# scheme.net
KiCad netlist of a schematic drawn in EAGLE
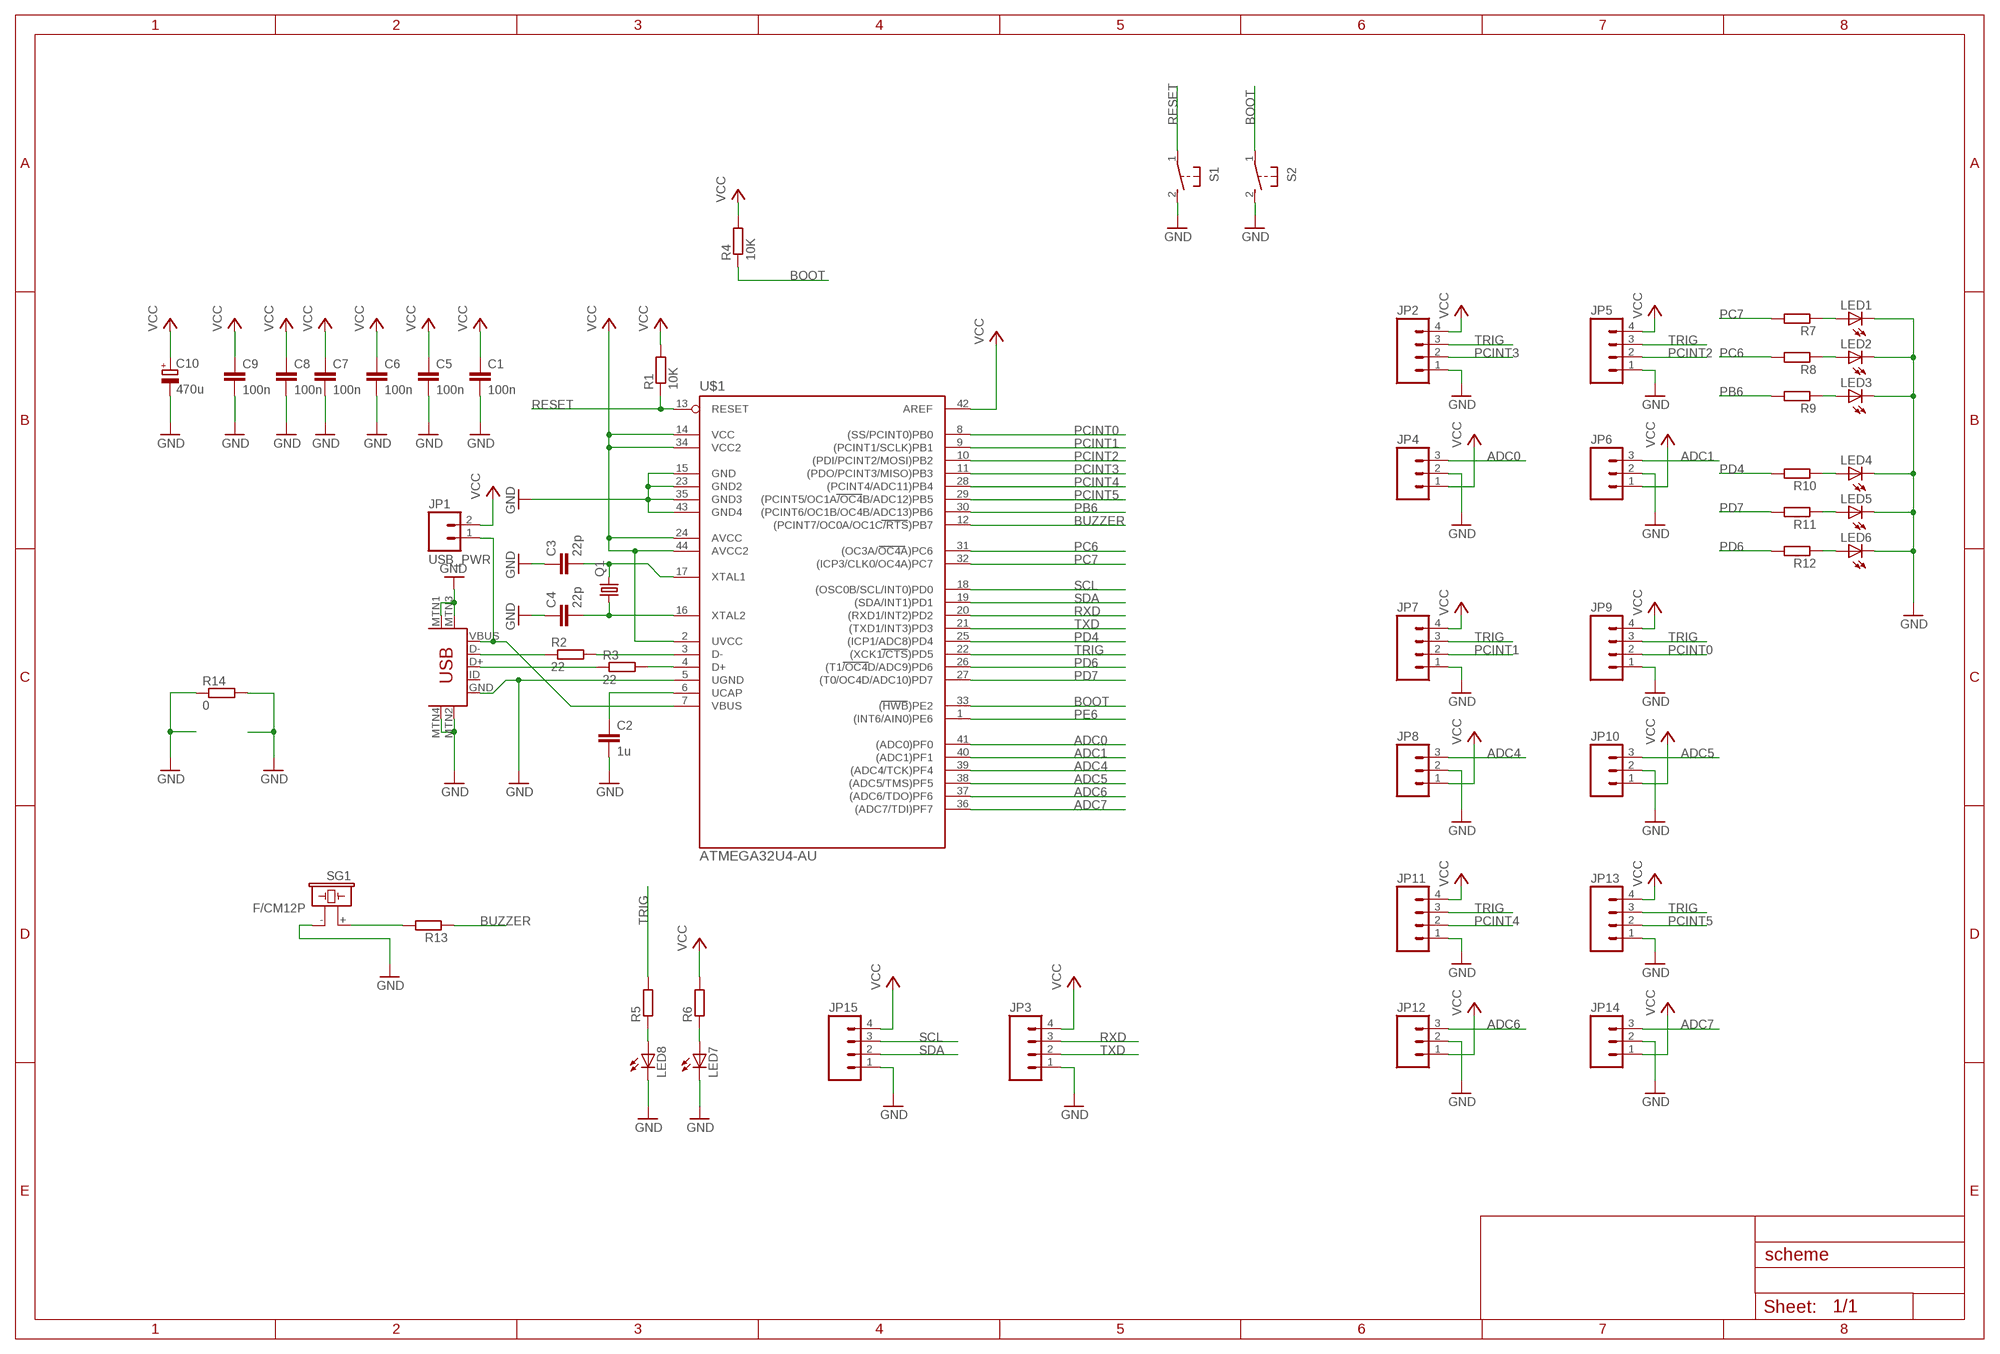
[diagram p0: schematic, sheet 1]

(export (version "E")
  (design (tool "Eeschema 10.0.6"))
  (components
    (comp (ref "C1")
      (value "100n")
      (footprint "eagle-import:C0805")
      (libsource (lib "eagle-import") (part "C-EUC0805"))
    )
    (comp (ref "C2")
      (value "1u")
      (footprint "eagle-import:C0805")
      (libsource (lib "eagle-import") (part "C-EUC0805"))
    )
    (comp (ref "C3")
      (value "22p")
      (footprint "eagle-import:C0805")
      (libsource (lib "eagle-import") (part "C-EUC0805"))
    )
    (comp (ref "C4")
      (value "22p")
      (footprint "eagle-import:C0805")
      (libsource (lib "eagle-import") (part "C-EUC0805"))
    )
    (comp (ref "C5")
      (value "100n")
      (footprint "eagle-import:C0805")
      (libsource (lib "eagle-import") (part "C-EUC0805"))
    )
    (comp (ref "C6")
      (value "100n")
      (footprint "eagle-import:C0805")
      (libsource (lib "eagle-import") (part "C-EUC0805"))
    )
    (comp (ref "C7")
      (value "100n")
      (footprint "eagle-import:C0805")
      (libsource (lib "eagle-import") (part "C-EUC0805"))
    )
    (comp (ref "C8")
      (value "100n")
      (footprint "eagle-import:C0805")
      (libsource (lib "eagle-import") (part "C-EUC0805"))
    )
    (comp (ref "C9")
      (value "100n")
      (footprint "eagle-import:C0805")
      (libsource (lib "eagle-import") (part "C-EUC0805"))
    )
    (comp (ref "C10")
      (value "470u")
      (footprint "eagle-import:E3,5-8")
      (libsource (lib "eagle-import") (part "CPOL-EUE3.5-8"))
    )
    (comp (ref "JP1")
      (value "USB_PWR")
      (footprint "eagle-import:1X02")
      (libsource (lib "eagle-import") (part "M02PTH"))
    )
    (comp (ref "JP2")
      (value "M04PTH")
      (footprint "eagle-import:1X04")
      (libsource (lib "eagle-import") (part "M04PTH"))
    )
    (comp (ref "JP3")
      (value "M04PTH")
      (footprint "eagle-import:1X04")
      (libsource (lib "eagle-import") (part "M04PTH"))
    )
    (comp (ref "JP4")
      (value "M03PTH")
      (footprint "eagle-import:1X03")
      (libsource (lib "eagle-import") (part "M03PTH"))
    )
    (comp (ref "JP5")
      (value "M04PTH")
      (footprint "eagle-import:1X04")
      (libsource (lib "eagle-import") (part "M04PTH"))
    )
    (comp (ref "JP6")
      (value "M03PTH")
      (footprint "eagle-import:1X03")
      (libsource (lib "eagle-import") (part "M03PTH"))
    )
    (comp (ref "JP7")
      (value "M04PTH")
      (footprint "eagle-import:1X04")
      (libsource (lib "eagle-import") (part "M04PTH"))
    )
    (comp (ref "JP8")
      (value "M03PTH")
      (footprint "eagle-import:1X03")
      (libsource (lib "eagle-import") (part "M03PTH"))
    )
    (comp (ref "JP9")
      (value "M04PTH")
      (footprint "eagle-import:1X04")
      (libsource (lib "eagle-import") (part "M04PTH"))
    )
    (comp (ref "JP10")
      (value "M03PTH")
      (footprint "eagle-import:1X03")
      (libsource (lib "eagle-import") (part "M03PTH"))
    )
    (comp (ref "JP11")
      (value "M04PTH")
      (footprint "eagle-import:1X04")
      (libsource (lib "eagle-import") (part "M04PTH"))
    )
    (comp (ref "JP12")
      (value "M03PTH")
      (footprint "eagle-import:1X03")
      (libsource (lib "eagle-import") (part "M03PTH"))
    )
    (comp (ref "JP13")
      (value "M04PTH")
      (footprint "eagle-import:1X04")
      (libsource (lib "eagle-import") (part "M04PTH"))
    )
    (comp (ref "JP14")
      (value "M03PTH")
      (footprint "eagle-import:1X03")
      (libsource (lib "eagle-import") (part "M03PTH"))
    )
    (comp (ref "JP15")
      (value "M04PTH")
      (footprint "eagle-import:1X04")
      (libsource (lib "eagle-import") (part "M04PTH"))
    )
    (comp (ref "LED1")
      (value "LEDSMT1206")
      (footprint "eagle-import:1206")
      (libsource (lib "eagle-import") (part "LEDSMT1206"))
    )
    (comp (ref "LED2")
      (value "LEDSMT1206")
      (footprint "eagle-import:1206")
      (libsource (lib "eagle-import") (part "LEDSMT1206"))
    )
    (comp (ref "LED3")
      (value "LEDSMT1206")
      (footprint "eagle-import:1206")
      (libsource (lib "eagle-import") (part "LEDSMT1206"))
    )
    (comp (ref "LED4")
      (value "LEDSMT1206")
      (footprint "eagle-import:1206")
      (libsource (lib "eagle-import") (part "LEDSMT1206"))
    )
    (comp (ref "LED5")
      (value "LEDSMT1206")
      (footprint "eagle-import:1206")
      (libsource (lib "eagle-import") (part "LEDSMT1206"))
    )
    (comp (ref "LED6")
      (value "LEDSMT1206")
      (footprint "eagle-import:1206")
      (libsource (lib "eagle-import") (part "LEDSMT1206"))
    )
    (comp (ref "LED7")
      (value "LEDSMT1206")
      (footprint "eagle-import:1206")
      (libsource (lib "eagle-import") (part "LEDSMT1206"))
    )
    (comp (ref "LED8")
      (value "LEDSMT1206")
      (footprint "eagle-import:1206")
      (libsource (lib "eagle-import") (part "LEDSMT1206"))
    )
    (comp (ref "Q1")
      (value "CRYSTALHC49S")
      (footprint "eagle-import:HC49_S")
      (libsource (lib "eagle-import") (part "CRYSTALHC49S"))
    )
    (comp (ref "R1")
      (value "10K")
      (footprint "eagle-import:R0805")
      (libsource (lib "eagle-import") (part "R-EU_R0805"))
    )
    (comp (ref "R2")
      (value "22")
      (footprint "eagle-import:R0805")
      (libsource (lib "eagle-import") (part "R-EU_R0805"))
    )
    (comp (ref "R3")
      (value "22")
      (footprint "eagle-import:R0805")
      (libsource (lib "eagle-import") (part "R-EU_R0805"))
    )
    (comp (ref "R4")
      (value "10K")
      (footprint "eagle-import:R0805")
      (libsource (lib "eagle-import") (part "R-EU_R0805"))
    )
    (comp (ref "R5")
      (value "R-EU_M0805")
      (footprint "eagle-import:M0805")
      (libsource (lib "eagle-import") (part "R-EU_M0805"))
    )
    (comp (ref "R6")
      (value "R-EU_M0805")
      (footprint "eagle-import:M0805")
      (libsource (lib "eagle-import") (part "R-EU_M0805"))
    )
    (comp (ref "R7")
      (value "R-EU_M0805")
      (footprint "eagle-import:M0805")
      (libsource (lib "eagle-import") (part "R-EU_M0805"))
    )
    (comp (ref "R8")
      (value "R-EU_M0805")
      (footprint "eagle-import:M0805")
      (libsource (lib "eagle-import") (part "R-EU_M0805"))
    )
    (comp (ref "R9")
      (value "R-EU_M0805")
      (footprint "eagle-import:M0805")
      (libsource (lib "eagle-import") (part "R-EU_M0805"))
    )
    (comp (ref "R10")
      (value "R-EU_M0805")
      (footprint "eagle-import:M0805")
      (libsource (lib "eagle-import") (part "R-EU_M0805"))
    )
    (comp (ref "R11")
      (value "R-EU_M0805")
      (footprint "eagle-import:M0805")
      (libsource (lib "eagle-import") (part "R-EU_M0805"))
    )
    (comp (ref "R12")
      (value "R-EU_M0805")
      (footprint "eagle-import:M0805")
      (libsource (lib "eagle-import") (part "R-EU_M0805"))
    )
    (comp (ref "R13")
      (value "R-EU_M0805")
      (footprint "eagle-import:M0805")
      (libsource (lib "eagle-import") (part "R-EU_M0805"))
    )
    (comp (ref "R14")
      (value "0")
      (footprint "eagle-import:M1206")
      (libsource (lib "eagle-import") (part "R-EU_M1206"))
    )
    (comp (ref "S1")
      (value "31-XX")
      (footprint "eagle-import:B3F-31XX")
      (fields (field (name "MPN") "B3F-3100"))
      (libsource (lib "eagle-import") (part "31-XX"))
    )
    (comp (ref "S2")
      (value "31-XX")
      (footprint "eagle-import:B3F-31XX")
      (fields (field (name "MPN") "B3F-3100"))
      (libsource (lib "eagle-import") (part "31-XX"))
    )
    (comp (ref "SG1")
      (value "F/CM12P")
      (footprint "eagle-import:F_CM12P")
      (libsource (lib "eagle-import") (part "F/CM12P"))
    )
    (comp (ref "U$1")
      (value "ATMEGA32U4-AU")
      (footprint "eagle-import:TQFP44")
      (libsource (lib "eagle-import") (part "ATMEGA32U4-AU"))
    )
    (comp (ref "U$2")
      (value "USB-MINIB-5PIN")
      (footprint "eagle-import:USB-MINIB")
      (libsource (lib "eagle-import") (part "USB-MINIB-5PIN"))
    )
  )
  (nets
    (net (code "1") (name "/ADC0") (class "Default")
      (node (ref "JP4") (pin "3") (pinfunction "3_3") (pintype "passive"))
      (node (ref "U$1") (pin "41") (pinfunction "(ADC0)PF0_41") (pintype "bidirectional"))
    )
    (net (code "2") (name "/ADC1") (class "Default")
      (node (ref "JP6") (pin "3") (pinfunction "3_3") (pintype "passive"))
      (node (ref "U$1") (pin "40") (pinfunction "(ADC1)PF1_40") (pintype "bidirectional"))
    )
    (net (code "3") (name "/ADC4") (class "Default")
      (node (ref "JP8") (pin "3") (pinfunction "3_3") (pintype "passive"))
      (node (ref "U$1") (pin "39") (pinfunction "(ADC4/TCK)PF4_39") (pintype "bidirectional"))
    )
    (net (code "4") (name "/ADC5") (class "Default")
      (node (ref "JP10") (pin "3") (pinfunction "3_3") (pintype "passive"))
      (node (ref "U$1") (pin "38") (pinfunction "(ADC5/TMS)PF5_38") (pintype "bidirectional"))
    )
    (net (code "5") (name "/ADC6") (class "Default")
      (node (ref "JP12") (pin "3") (pinfunction "3_3") (pintype "passive"))
      (node (ref "U$1") (pin "37") (pinfunction "(ADC6/TDO)PF6_37") (pintype "bidirectional"))
    )
    (net (code "6") (name "/ADC7") (class "Default")
      (node (ref "JP14") (pin "3") (pinfunction "3_3") (pintype "passive"))
      (node (ref "U$1") (pin "36") (pinfunction "(ADC7/TDI)PF7_36") (pintype "bidirectional"))
    )
    (net (code "7") (name "/BOOT") (class "Default")
      (node (ref "R4") (pin "1") (pinfunction "1_1") (pintype "passive"))
      (node (ref "S2") (pin "1") (pinfunction "P_1") (pintype "passive"))
      (node (ref "U$1") (pin "33") (pinfunction "(HWB)PE2_33") (pintype "bidirectional"))
    )
    (net (code "8") (name "/BUZZER") (class "Default")
      (node (ref "R13") (pin "1") (pinfunction "1_1") (pintype "passive"))
      (node (ref "U$1") (pin "12") (pinfunction "(PCINT7/OC0A/OC1C/RTS)PB7_12") (pintype "bidirectional"))
    )
    (net (code "9") (name "/PB6") (class "Default")
      (node (ref "R9") (pin "2") (pinfunction "2_2") (pintype "passive"))
      (node (ref "U$1") (pin "30") (pinfunction "(PCINT6/OC1B/OC4B/ADC13)PB6_30") (pintype "bidirectional"))
    )
    (net (code "10") (name "/PC6") (class "Default")
      (node (ref "R8") (pin "2") (pinfunction "2_2") (pintype "passive"))
      (node (ref "U$1") (pin "31") (pinfunction "(OC3A/OC4A)PC6_31") (pintype "bidirectional"))
    )
    (net (code "11") (name "/PC7") (class "Default")
      (node (ref "R7") (pin "2") (pinfunction "2_2") (pintype "passive"))
      (node (ref "U$1") (pin "32") (pinfunction "(ICP3/CLK0/OC4A)PC7_32") (pintype "bidirectional"))
    )
    (net (code "12") (name "/PCINT0") (class "Default")
      (node (ref "JP9") (pin "2") (pinfunction "2_2") (pintype "passive"))
      (node (ref "U$1") (pin "8") (pinfunction "(SS/PCINT0)PB0_8") (pintype "bidirectional"))
    )
    (net (code "13") (name "/PCINT1") (class "Default")
      (node (ref "JP7") (pin "2") (pinfunction "2_2") (pintype "passive"))
      (node (ref "U$1") (pin "9") (pinfunction "(PCINT1/SCLK)PB1_9") (pintype "bidirectional"))
    )
    (net (code "14") (name "/PCINT2") (class "Default")
      (node (ref "JP5") (pin "2") (pinfunction "2_2") (pintype "passive"))
      (node (ref "U$1") (pin "10") (pinfunction "(PDI/PCINT2/MOSI)PB2_10") (pintype "bidirectional"))
    )
    (net (code "15") (name "/PCINT3") (class "Default")
      (node (ref "JP2") (pin "2") (pinfunction "2_2") (pintype "passive"))
      (node (ref "U$1") (pin "11") (pinfunction "(PDO/PCINT3/MISO)PB3_11") (pintype "bidirectional"))
    )
    (net (code "16") (name "/PCINT4") (class "Default")
      (node (ref "JP11") (pin "2") (pinfunction "2_2") (pintype "passive"))
      (node (ref "U$1") (pin "28") (pinfunction "(PCINT4/ADC11)PB4_28") (pintype "bidirectional"))
    )
    (net (code "17") (name "/PCINT5") (class "Default")
      (node (ref "JP13") (pin "2") (pinfunction "2_2") (pintype "passive"))
      (node (ref "U$1") (pin "29") (pinfunction "(PCINT5/OC1A/OC4B/ADC12)PB5_29") (pintype "bidirectional"))
    )
    (net (code "18") (name "/PD4") (class "Default")
      (node (ref "R10") (pin "2") (pinfunction "2_2") (pintype "passive"))
      (node (ref "U$1") (pin "25") (pinfunction "(ICP1/ADC8)PD4_25") (pintype "bidirectional"))
    )
    (net (code "19") (name "/PD6") (class "Default")
      (node (ref "R12") (pin "2") (pinfunction "2_2") (pintype "passive"))
      (node (ref "U$1") (pin "26") (pinfunction "(T1/OC4D/ADC9)PD6_26") (pintype "bidirectional"))
    )
    (net (code "20") (name "/PD7") (class "Default")
      (node (ref "R11") (pin "2") (pinfunction "2_2") (pintype "passive"))
      (node (ref "U$1") (pin "27") (pinfunction "(T0/OC4D/ADC10)PD7_27") (pintype "bidirectional"))
    )
    (net (code "21") (name "/PE6") (class "Default")
      (node (ref "U$1") (pin "1") (pinfunction "(INT6/AIN0)PE6_1") (pintype "bidirectional"))
    )
    (net (code "22") (name "/RESET") (class "Default")
      (node (ref "R1") (pin "1") (pinfunction "1_1") (pintype "passive"))
      (node (ref "S1") (pin "1") (pinfunction "P_1") (pintype "passive"))
      (node (ref "U$1") (pin "13") (pinfunction "RESET_13") (pintype "bidirectional"))
    )
    (net (code "23") (name "/RXD") (class "Default")
      (node (ref "JP3") (pin "3") (pinfunction "3_3") (pintype "passive"))
      (node (ref "U$1") (pin "20") (pinfunction "(RXD1/INT2)PD2_20") (pintype "bidirectional"))
    )
    (net (code "24") (name "/SCL") (class "Default")
      (node (ref "JP15") (pin "3") (pinfunction "3_3") (pintype "passive"))
      (node (ref "U$1") (pin "18") (pinfunction "(OSC0B/SCL/INT0)PD0_18") (pintype "bidirectional"))
    )
    (net (code "25") (name "/SDA") (class "Default")
      (node (ref "JP15") (pin "2") (pinfunction "2_2") (pintype "passive"))
      (node (ref "U$1") (pin "19") (pinfunction "(SDA/INT1)PD1_19") (pintype "bidirectional"))
    )
    (net (code "26") (name "/TRIG") (class "Default")
      (node (ref "JP11") (pin "3") (pinfunction "3_3") (pintype "passive"))
      (node (ref "JP13") (pin "3") (pinfunction "3_3") (pintype "passive"))
      (node (ref "JP2") (pin "3") (pinfunction "3_3") (pintype "passive"))
      (node (ref "JP5") (pin "3") (pinfunction "3_3") (pintype "passive"))
      (node (ref "JP7") (pin "3") (pinfunction "3_3") (pintype "passive"))
      (node (ref "JP9") (pin "3") (pinfunction "3_3") (pintype "passive"))
      (node (ref "R5") (pin "2") (pinfunction "2_2") (pintype "passive"))
      (node (ref "U$1") (pin "22") (pinfunction "(XCK1/CTS)PD5_22") (pintype "bidirectional"))
    )
    (net (code "27") (name "/TXD") (class "Default")
      (node (ref "JP3") (pin "2") (pinfunction "2_2") (pintype "passive"))
      (node (ref "U$1") (pin "21") (pinfunction "(TXD1/INT3)PD3_21") (pintype "bidirectional"))
    )
    (net (code "28") (name "GND") (class "Default")
      (node (ref "C1") (pin "2") (pinfunction "2_2") (pintype "passive"))
      (node (ref "C10") (pin "-") (pinfunction "-_-") (pintype "passive"))
      (node (ref "C2") (pin "2") (pinfunction "2_2") (pintype "passive"))
      (node (ref "C3") (pin "1") (pinfunction "1_1") (pintype "passive"))
      (node (ref "C4") (pin "1") (pinfunction "1_1") (pintype "passive"))
      (node (ref "C5") (pin "2") (pinfunction "2_2") (pintype "passive"))
      (node (ref "C6") (pin "2") (pinfunction "2_2") (pintype "passive"))
      (node (ref "C7") (pin "2") (pinfunction "2_2") (pintype "passive"))
      (node (ref "C8") (pin "2") (pinfunction "2_2") (pintype "passive"))
      (node (ref "C9") (pin "2") (pinfunction "2_2") (pintype "passive"))
      (node (ref "JP10") (pin "2") (pinfunction "2_2") (pintype "passive"))
      (node (ref "JP11") (pin "1") (pinfunction "1_1") (pintype "passive"))
      (node (ref "JP12") (pin "2") (pinfunction "2_2") (pintype "passive"))
      (node (ref "JP13") (pin "1") (pinfunction "1_1") (pintype "passive"))
      (node (ref "JP14") (pin "2") (pinfunction "2_2") (pintype "passive"))
      (node (ref "JP15") (pin "1") (pinfunction "1_1") (pintype "passive"))
      (node (ref "JP2") (pin "1") (pinfunction "1_1") (pintype "passive"))
      (node (ref "JP3") (pin "1") (pinfunction "1_1") (pintype "passive"))
      (node (ref "JP4") (pin "2") (pinfunction "2_2") (pintype "passive"))
      (node (ref "JP5") (pin "1") (pinfunction "1_1") (pintype "passive"))
      (node (ref "JP6") (pin "2") (pinfunction "2_2") (pintype "passive"))
      (node (ref "JP7") (pin "1") (pinfunction "1_1") (pintype "passive"))
      (node (ref "JP8") (pin "2") (pinfunction "2_2") (pintype "passive"))
      (node (ref "JP9") (pin "1") (pinfunction "1_1") (pintype "passive"))
      (node (ref "LED1") (pin "C") (pinfunction "C_C") (pintype "passive"))
      (node (ref "LED2") (pin "C") (pinfunction "C_C") (pintype "passive"))
      (node (ref "LED3") (pin "C") (pinfunction "C_C") (pintype "passive"))
      (node (ref "LED4") (pin "C") (pinfunction "C_C") (pintype "passive"))
      (node (ref "LED5") (pin "C") (pinfunction "C_C") (pintype "passive"))
      (node (ref "LED6") (pin "C") (pinfunction "C_C") (pintype "passive"))
      (node (ref "LED7") (pin "C") (pinfunction "C_C") (pintype "passive"))
      (node (ref "LED8") (pin "C") (pinfunction "C_C") (pintype "passive"))
      (node (ref "R14") (pin "1") (pinfunction "1_1") (pintype "passive"))
      (node (ref "R14") (pin "2") (pinfunction "2_2") (pintype "passive"))
      (node (ref "S1") (pin "2") (pinfunction "S_2") (pintype "passive"))
      (node (ref "S2") (pin "2") (pinfunction "S_2") (pintype "passive"))
      (node (ref "SG1") (pin "-") (pinfunction "2_-") (pintype "passive"))
      (node (ref "U$1") (pin "15") (pinfunction "GND_15") (pintype "bidirectional"))
      (node (ref "U$1") (pin "23") (pinfunction "GND2_23") (pintype "bidirectional"))
      (node (ref "U$1") (pin "35") (pinfunction "GND3_35") (pintype "bidirectional"))
      (node (ref "U$1") (pin "43") (pinfunction "GND4_43") (pintype "bidirectional"))
      (node (ref "U$1") (pin "5") (pinfunction "UGND_5") (pintype "bidirectional"))
      (node (ref "U$2") (pin "GND") (pinfunction "GND_GND") (pintype "bidirectional"))
      (node (ref "U$2") (pin "MTN1") (pinfunction "MTN2_MTN1") (pintype "bidirectional"))
      (node (ref "U$2") (pin "MTN2") (pinfunction "MTN3_MTN2") (pintype "bidirectional"))
      (node (ref "U$2") (pin "MTN3") (pinfunction "MTN1_MTN3") (pintype "bidirectional"))
      (node (ref "U$2") (pin "MTN4") (pinfunction "MTN4_MTN4") (pintype "bidirectional"))
    )
    (net (code "29") (name "Net-(LED1-PadA)") (class "Default")
      (node (ref "LED1") (pin "A") (pinfunction "A_A") (pintype "passive"))
      (node (ref "R7") (pin "1") (pinfunction "1_1") (pintype "passive"))
    )
    (net (code "30") (name "Net-(LED2-PadA)") (class "Default")
      (node (ref "LED2") (pin "A") (pinfunction "A_A") (pintype "passive"))
      (node (ref "R8") (pin "1") (pinfunction "1_1") (pintype "passive"))
    )
    (net (code "31") (name "Net-(LED3-PadA)") (class "Default")
      (node (ref "LED3") (pin "A") (pinfunction "A_A") (pintype "passive"))
      (node (ref "R9") (pin "1") (pinfunction "1_1") (pintype "passive"))
    )
    (net (code "32") (name "Net-(LED4-PadA)") (class "Default")
      (node (ref "LED4") (pin "A") (pinfunction "A_A") (pintype "passive"))
      (node (ref "R10") (pin "1") (pinfunction "1_1") (pintype "passive"))
    )
    (net (code "33") (name "Net-(LED5-PadA)") (class "Default")
      (node (ref "LED5") (pin "A") (pinfunction "A_A") (pintype "passive"))
      (node (ref "R11") (pin "1") (pinfunction "1_1") (pintype "passive"))
    )
    (net (code "34") (name "Net-(LED6-PadA)") (class "Default")
      (node (ref "LED6") (pin "A") (pinfunction "A_A") (pintype "passive"))
      (node (ref "R12") (pin "1") (pinfunction "1_1") (pintype "passive"))
    )
    (net (code "35") (name "Net-(LED7-PadA)") (class "Default")
      (node (ref "LED7") (pin "A") (pinfunction "A_A") (pintype "passive"))
      (node (ref "R6") (pin "1") (pinfunction "1_1") (pintype "passive"))
    )
    (net (code "36") (name "Net-(LED8-PadA)") (class "Default")
      (node (ref "LED8") (pin "A") (pinfunction "A_A") (pintype "passive"))
      (node (ref "R5") (pin "1") (pinfunction "1_1") (pintype "passive"))
    )
    (net (code "37") (name "Net-(R2-Pad1)") (class "Default")
      (node (ref "R2") (pin "1") (pinfunction "1_1") (pintype "passive"))
      (node (ref "U$2") (pin "D-") (pinfunction "D-_D-") (pintype "bidirectional"))
    )
    (net (code "38") (name "Net-(R3-Pad1)") (class "Default")
      (node (ref "R3") (pin "1") (pinfunction "1_1") (pintype "passive"))
      (node (ref "U$2") (pin "D+") (pinfunction "D+_D+") (pintype "bidirectional"))
    )
    (net (code "39") (name "Net-(SG1-1)") (class "Default")
      (node (ref "R13") (pin "2") (pinfunction "2_2") (pintype "passive"))
      (node (ref "SG1") (pin "+") (pinfunction "1_+") (pintype "passive"))
    )
    (net (code "40") (name "Net-(U$1-D+)") (class "Default")
      (node (ref "R3") (pin "2") (pinfunction "2_2") (pintype "passive"))
      (node (ref "U$1") (pin "4") (pinfunction "D+_4") (pintype "bidirectional"))
    )
    (net (code "41") (name "Net-(U$1-D-)") (class "Default")
      (node (ref "R2") (pin "2") (pinfunction "2_2") (pintype "passive"))
      (node (ref "U$1") (pin "3") (pinfunction "D-_3") (pintype "bidirectional"))
    )
    (net (code "42") (name "Net-(U$1-UCAP)") (class "Default")
      (node (ref "C2") (pin "1") (pinfunction "1_1") (pintype "passive"))
      (node (ref "U$1") (pin "6") (pinfunction "UCAP_6") (pintype "bidirectional"))
    )
    (net (code "43") (name "Net-(U$1-VBUS)") (class "Default")
      (node (ref "JP1") (pin "1") (pinfunction "1_1") (pintype "passive"))
      (node (ref "U$1") (pin "7") (pinfunction "VBUS_7") (pintype "bidirectional"))
      (node (ref "U$2") (pin "VBUS") (pinfunction "VBUS_VBUS") (pintype "bidirectional"))
    )
    (net (code "44") (name "Net-(U$1-XTAL1)") (class "Default")
      (node (ref "C3") (pin "2") (pinfunction "2_2") (pintype "passive"))
      (node (ref "Q1") (pin "2") (pinfunction "2_2") (pintype "passive"))
      (node (ref "U$1") (pin "17") (pinfunction "XTAL1_17") (pintype "bidirectional"))
    )
    (net (code "45") (name "Net-(U$1-XTAL2)") (class "Default")
      (node (ref "C4") (pin "2") (pinfunction "2_2") (pintype "passive"))
      (node (ref "Q1") (pin "1") (pinfunction "1_1") (pintype "passive"))
      (node (ref "U$1") (pin "16") (pinfunction "XTAL2_16") (pintype "bidirectional"))
    )
    (net (code "46") (name "VCC") (class "Default")
      (node (ref "C1") (pin "1") (pinfunction "1_1") (pintype "passive"))
      (node (ref "C10") (pin "+") (pinfunction "+_+") (pintype "passive"))
      (node (ref "C5") (pin "1") (pinfunction "1_1") (pintype "passive"))
      (node (ref "C6") (pin "1") (pinfunction "1_1") (pintype "passive"))
      (node (ref "C7") (pin "1") (pinfunction "1_1") (pintype "passive"))
      (node (ref "C8") (pin "1") (pinfunction "1_1") (pintype "passive"))
      (node (ref "C9") (pin "1") (pinfunction "1_1") (pintype "passive"))
      (node (ref "JP1") (pin "2") (pinfunction "2_2") (pintype "passive"))
      (node (ref "JP10") (pin "1") (pinfunction "1_1") (pintype "passive"))
      (node (ref "JP11") (pin "4") (pinfunction "4_4") (pintype "passive"))
      (node (ref "JP12") (pin "1") (pinfunction "1_1") (pintype "passive"))
      (node (ref "JP13") (pin "4") (pinfunction "4_4") (pintype "passive"))
      (node (ref "JP14") (pin "1") (pinfunction "1_1") (pintype "passive"))
      (node (ref "JP15") (pin "4") (pinfunction "4_4") (pintype "passive"))
      (node (ref "JP2") (pin "4") (pinfunction "4_4") (pintype "passive"))
      (node (ref "JP3") (pin "4") (pinfunction "4_4") (pintype "passive"))
      (node (ref "JP4") (pin "1") (pinfunction "1_1") (pintype "passive"))
      (node (ref "JP5") (pin "4") (pinfunction "4_4") (pintype "passive"))
      (node (ref "JP6") (pin "1") (pinfunction "1_1") (pintype "passive"))
      (node (ref "JP7") (pin "4") (pinfunction "4_4") (pintype "passive"))
      (node (ref "JP8") (pin "1") (pinfunction "1_1") (pintype "passive"))
      (node (ref "JP9") (pin "4") (pinfunction "4_4") (pintype "passive"))
      (node (ref "R1") (pin "2") (pinfunction "2_2") (pintype "passive"))
      (node (ref "R4") (pin "2") (pinfunction "2_2") (pintype "passive"))
      (node (ref "R6") (pin "2") (pinfunction "2_2") (pintype "passive"))
      (node (ref "U$1") (pin "14") (pinfunction "VCC_14") (pintype "bidirectional"))
      (node (ref "U$1") (pin "2") (pinfunction "UVCC_2") (pintype "bidirectional"))
      (node (ref "U$1") (pin "24") (pinfunction "AVCC_24") (pintype "bidirectional"))
      (node (ref "U$1") (pin "34") (pinfunction "VCC2_34") (pintype "bidirectional"))
      (node (ref "U$1") (pin "42") (pinfunction "AREF_42") (pintype "bidirectional"))
      (node (ref "U$1") (pin "44") (pinfunction "AVCC2_44") (pintype "bidirectional"))
    )
    (net (code "47") (name "unconnected-(U$2-PadID)") (class "Default")
      (node (ref "U$2") (pin "ID") (pinfunction "ID_ID") (pintype "bidirectional"))
    )
  )
)
